# old_line_kick.net
KiCad netlist of a schematic drawn in EAGLE
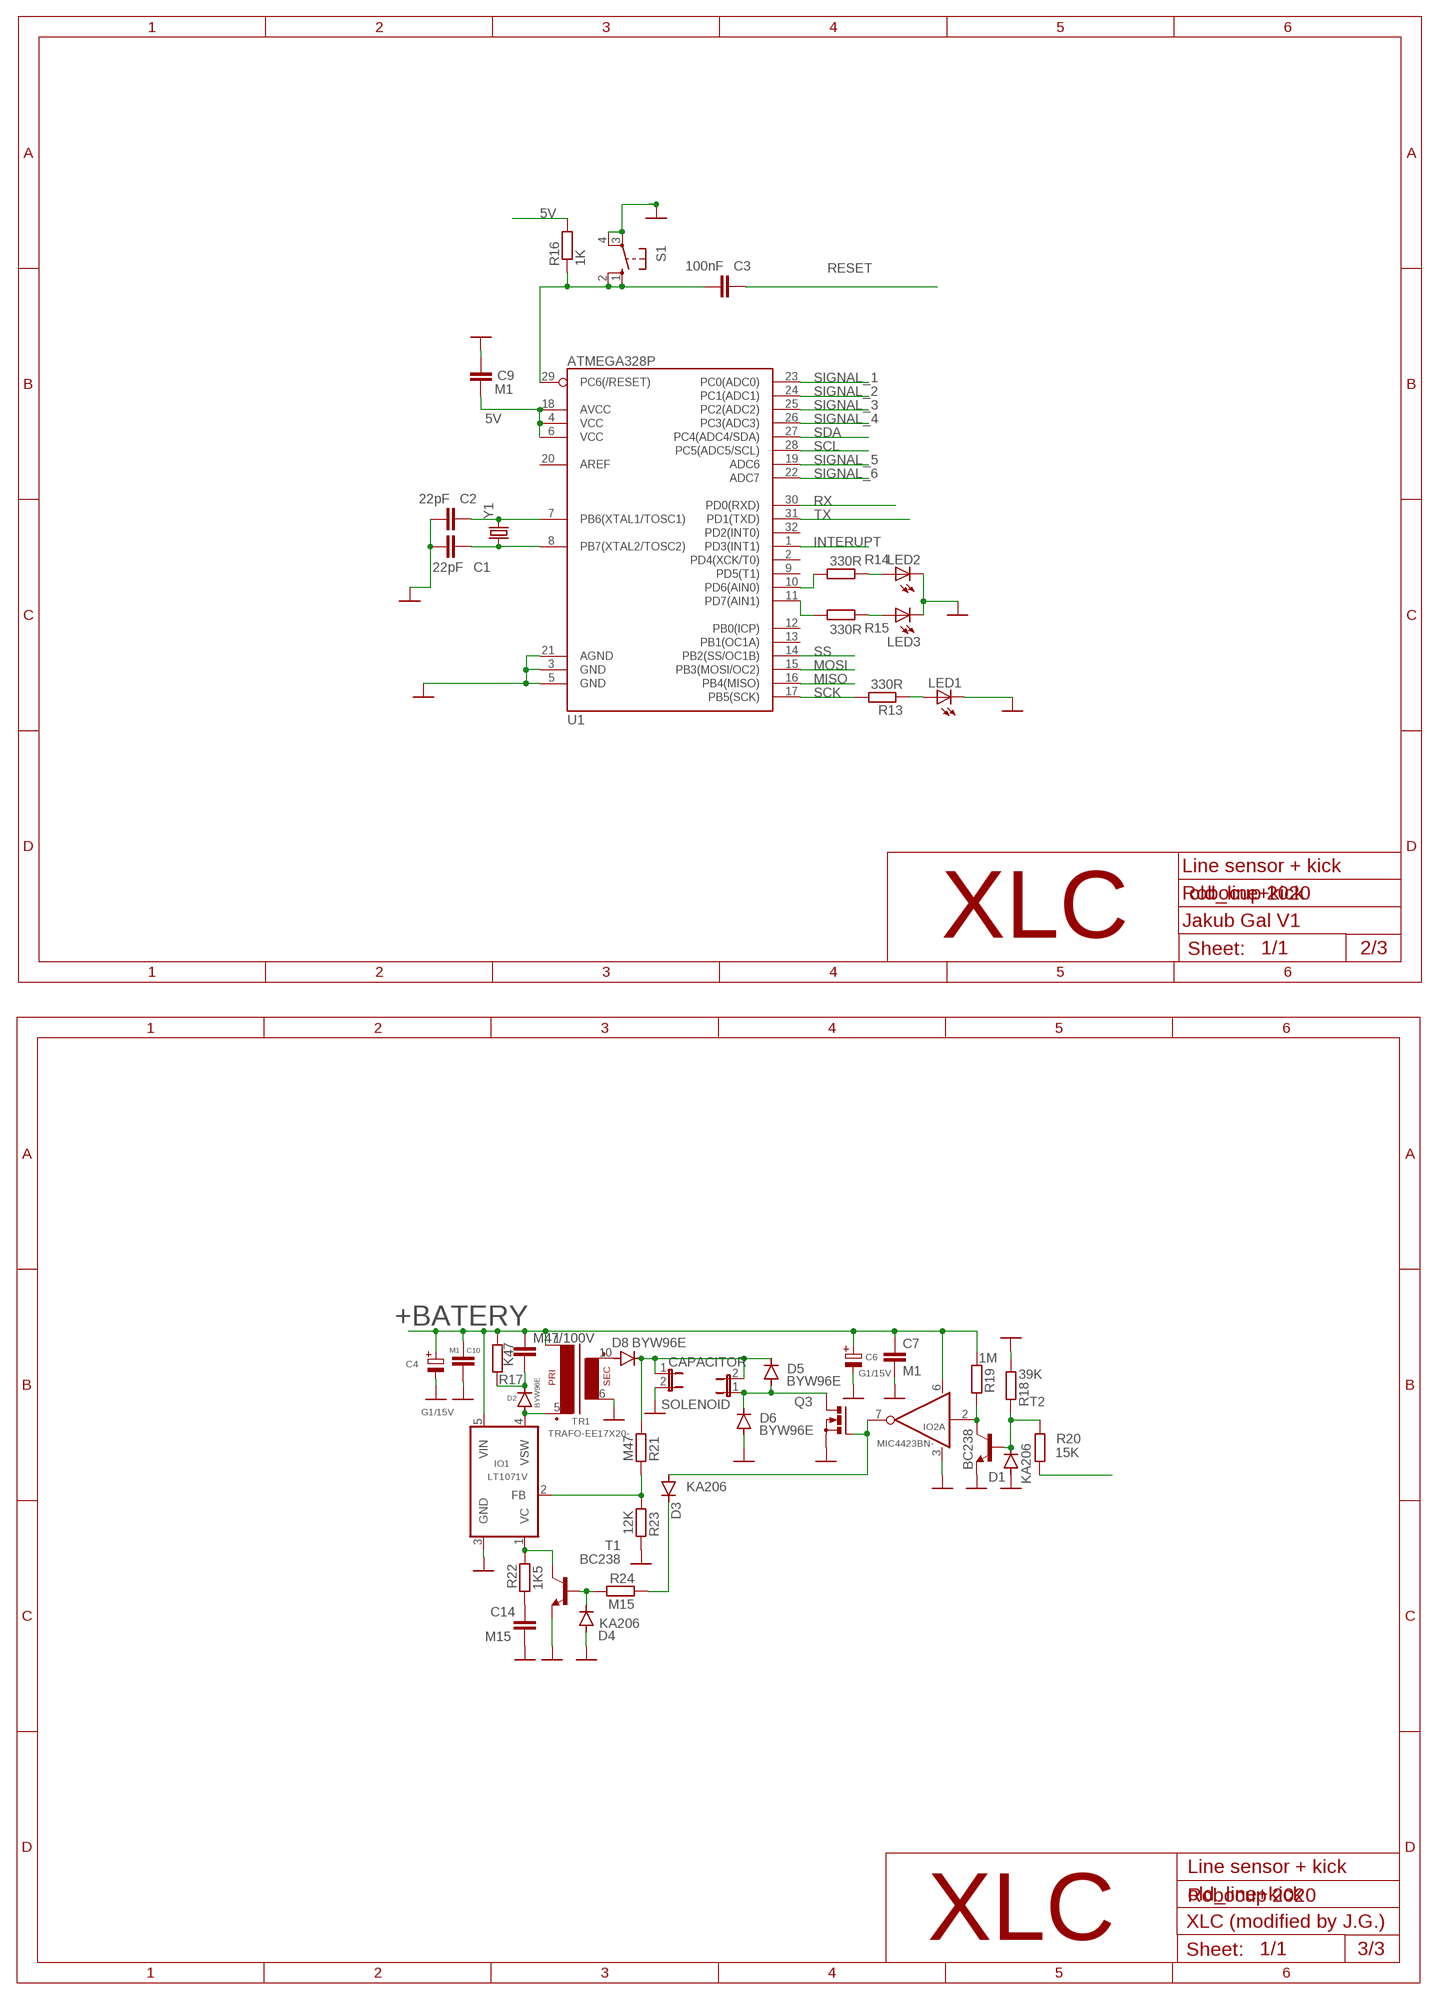
[diagram p0: schematic, sheet 1, part 1 of 2]
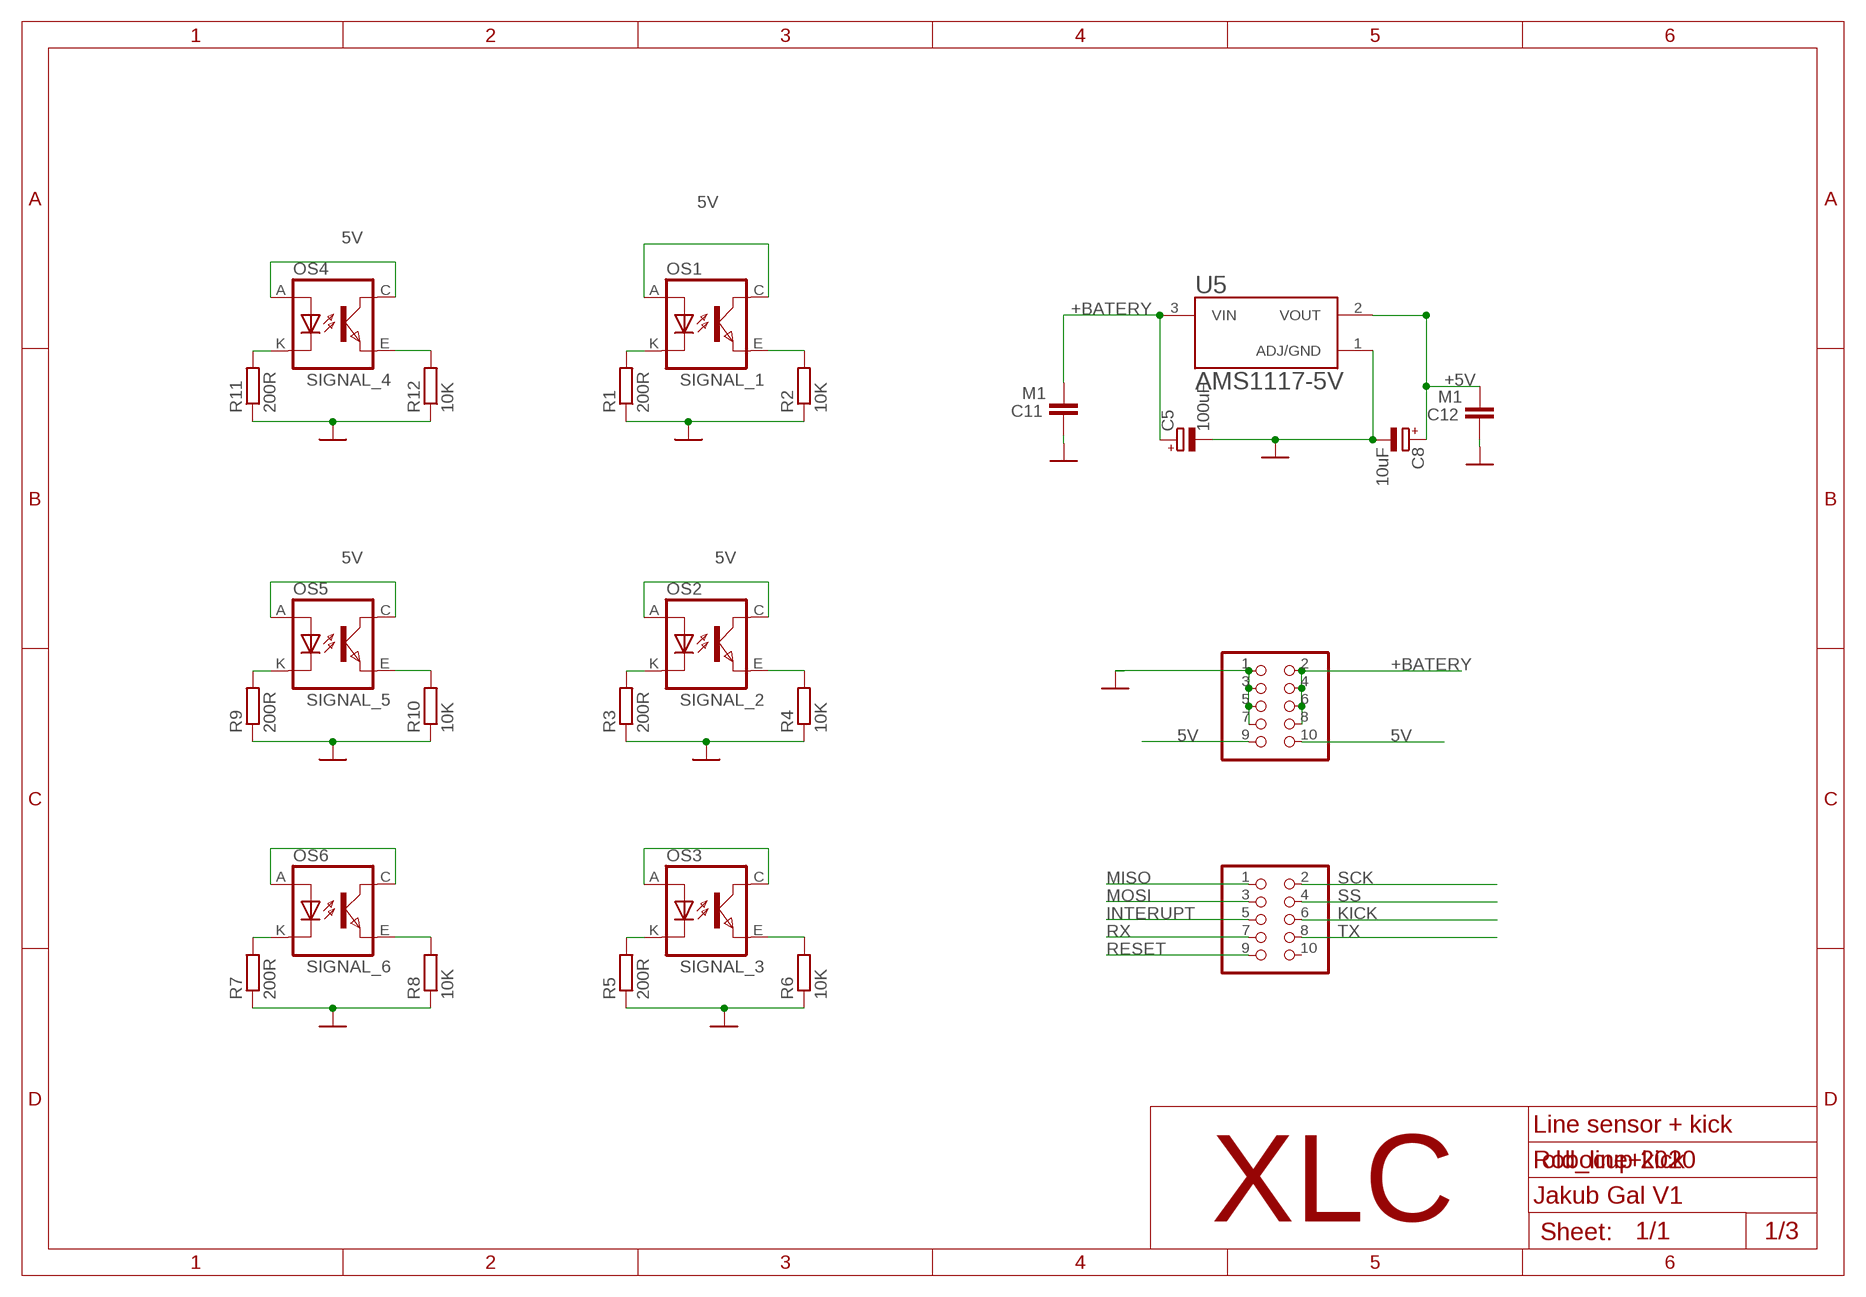
[diagram p1: schematic, sheet 1, part 2 of 2]

(export (version "E")
  (design (tool "Eeschema 10.0.6"))
  (components
    (comp (ref "C1")
      (value "22pF")
      (footprint "eagle-import:C0603")
      (libsource (lib "eagle-import") (part "C-EUC0603"))
    )
    (comp (ref "C2")
      (value "22pF")
      (footprint "eagle-import:C0603")
      (libsource (lib "eagle-import") (part "C-EUC0603"))
    )
    (comp (ref "C3")
      (value "100nF")
      (footprint "eagle-import:C0603")
      (libsource (lib "eagle-import") (part "C-EUC0603"))
    )
    (comp (ref "C4")
      (value "G1/15V")
      (footprint "eagle-import:E-2,5_7-RAD")
      (libsource (lib "eagle-import") (part "KOND-ELEKT-2,5/7"))
    )
    (comp (ref "C5")
      (value "100uF")
      (footprint "eagle-import:UD-6,3X7,7_NICHICON")
      (libsource (lib "eagle-import") (part "CPOL-EUUD-6,3X7,7"))
    )
    (comp (ref "C6")
      (value "G1/15V")
      (footprint "eagle-import:E-2,5_7-RAD")
      (libsource (lib "eagle-import") (part "KOND-ELEKT-2,5/7"))
    )
    (comp (ref "C7")
      (value "M1")
      (footprint "eagle-import:C0805K")
      (libsource (lib "eagle-import") (part "resistor_C-EUC0805K"))
    )
    (comp (ref "C8")
      (value "10uF")
      (footprint "eagle-import:UD-4X5,8_NICHICON")
      (libsource (lib "eagle-import") (part "CPOL-EUUD-4X5,8"))
    )
    (comp (ref "C9")
      (value "M1")
      (footprint "eagle-import:C0603")
      (libsource (lib "eagle-import") (part "C-EUC0603"))
    )
    (comp (ref "C10")
      (value "M1")
      (footprint "eagle-import:C0805K")
      (libsource (lib "eagle-import") (part "resistor_C-EUC0805K"))
    )
    (comp (ref "C11")
      (value "M1")
      (footprint "eagle-import:C0603")
      (libsource (lib "eagle-import") (part "C-EUC0603"))
    )
    (comp (ref "C12")
      (value "M1")
      (footprint "eagle-import:C0603")
      (libsource (lib "eagle-import") (part "C-EUC0603"))
    )
    (comp (ref "C14")
      (value "M15")
      (footprint "eagle-import:C0805K")
      (libsource (lib "eagle-import") (part "resistor_C-EUC0805K"))
    )
    (comp (ref "CAPACITOR")
      (value "JP1E")
      (footprint "eagle-import:JP1")
      (libsource (lib "eagle-import") (part "JP1E"))
    )
    (comp (ref "D1")
      (value "KA206")
      (footprint "eagle-import:D-7.5")
      (libsource (lib "eagle-import") (part "DIODE-D-7.5"))
    )
    (comp (ref "D2")
      (value "BYW96E")
      (footprint "eagle-import:SOD64-10")
      (libsource (lib "eagle-import") (part "BYW96"))
    )
    (comp (ref "D3")
      (value "KA206")
      (footprint "eagle-import:D-7.5")
      (libsource (lib "eagle-import") (part "DIODE-D-7.5"))
    )
    (comp (ref "D4")
      (value "KA206")
      (footprint "eagle-import:D-7.5")
      (libsource (lib "eagle-import") (part "DIODE-D-7.5"))
    )
    (comp (ref "D5")
      (value "BYW96E")
      (footprint "eagle-import:SOD64-10")
      (libsource (lib "eagle-import") (part "BYW96"))
    )
    (comp (ref "D6")
      (value "BYW96E")
      (footprint "eagle-import:SOD64-10")
      (libsource (lib "eagle-import") (part "BYW96"))
    )
    (comp (ref "D8")
      (value "BYW96E")
      (footprint "eagle-import:SOD64-10")
      (libsource (lib "eagle-import") (part "BYW96"))
    )
    (comp (ref "IO1")
      (value "LT1071V")
      (footprint "eagle-import:TO-220-5P")
      (libsource (lib "eagle-import") (part "LT1071V"))
    )
    (comp (ref "IO2")
      (value "MIC4423BN-")
      (footprint "eagle-import:DIL8")
      (libsource (lib "eagle-import") (part "MIC4423BN-"))
    )
    (comp (ref "JP2")
      (value "PINHD-2X5")
      (footprint "eagle-import:2X05")
      (libsource (lib "eagle-import") (part "PINHD-2X5"))
    )
    (comp (ref "JP3")
      (value "PINHD-2X5")
      (footprint "eagle-import:2X05")
      (libsource (lib "eagle-import") (part "PINHD-2X5"))
    )
    (comp (ref "LED1")
      (value "LEDCHIPLED_0603")
      (footprint "eagle-import:CHIPLED_0603")
      (libsource (lib "eagle-import") (part "LEDCHIPLED_0603"))
    )
    (comp (ref "LED2")
      (value "LEDCHIPLED_0603")
      (footprint "eagle-import:CHIPLED_0603")
      (libsource (lib "eagle-import") (part "LEDCHIPLED_0603"))
    )
    (comp (ref "LED3")
      (value "LEDCHIPLED_0603")
      (footprint "eagle-import:CHIPLED_0603")
      (libsource (lib "eagle-import") (part "LEDCHIPLED_0603"))
    )
    (comp (ref "M47/100V")
      (value "C-EUC0805K")
      (footprint "eagle-import:C0805K")
      (libsource (lib "eagle-import") (part "resistor_C-EUC0805K"))
    )
    (comp (ref "OS1")
      (value "TCRT5000")
      (footprint "eagle-import:TCRT5000")
      (libsource (lib "eagle-import") (part "TCRT5000"))
    )
    (comp (ref "OS2")
      (value "TCRT5000")
      (footprint "eagle-import:TCRT5000")
      (libsource (lib "eagle-import") (part "TCRT5000"))
    )
    (comp (ref "OS3")
      (value "TCRT5000")
      (footprint "eagle-import:TCRT5000")
      (libsource (lib "eagle-import") (part "TCRT5000"))
    )
    (comp (ref "OS4")
      (value "TCRT5000")
      (footprint "eagle-import:TCRT5000")
      (fields (field (name "SPICEPREFIX") "O"))
      (libsource (lib "eagle-import") (part "TCRT5000"))
    )
    (comp (ref "OS5")
      (value "TCRT5000")
      (footprint "eagle-import:TCRT5000")
      (libsource (lib "eagle-import") (part "TCRT5000"))
    )
    (comp (ref "OS6")
      (value "TCRT5000")
      (footprint "eagle-import:TCRT5000")
      (fields (field (name "SPICEPREFIX") "O"))
      (libsource (lib "eagle-import") (part "TCRT5000"))
    )
    (comp (ref "Q3")
      (value "PMOSFET_NTO220BV")
      (footprint "eagle-import:TO220BV")
      (libsource (lib "eagle-import") (part "PMOSFET_NTO220BV"))
    )
    (comp (ref "R1")
      (value "200R")
      (footprint "eagle-import:R0603")
      (libsource (lib "eagle-import") (part "R-EU_R0603"))
    )
    (comp (ref "R2")
      (value "10K")
      (footprint "eagle-import:R0603")
      (libsource (lib "eagle-import") (part "R-EU_R0603"))
    )
    (comp (ref "R3")
      (value "200R")
      (footprint "eagle-import:R0603")
      (libsource (lib "eagle-import") (part "R-EU_R0603"))
    )
    (comp (ref "R4")
      (value "10K")
      (footprint "eagle-import:R0603")
      (libsource (lib "eagle-import") (part "R-EU_R0603"))
    )
    (comp (ref "R5")
      (value "200R")
      (footprint "eagle-import:R0603")
      (libsource (lib "eagle-import") (part "R-EU_R0603"))
    )
    (comp (ref "R6")
      (value "10K")
      (footprint "eagle-import:R0603")
      (libsource (lib "eagle-import") (part "R-EU_R0603"))
    )
    (comp (ref "R7")
      (value "200R")
      (footprint "eagle-import:R0603")
      (libsource (lib "eagle-import") (part "R-EU_R0603"))
    )
    (comp (ref "R8")
      (value "10K")
      (footprint "eagle-import:R0603")
      (libsource (lib "eagle-import") (part "R-EU_R0603"))
    )
    (comp (ref "R9")
      (value "200R")
      (footprint "eagle-import:R0603")
      (libsource (lib "eagle-import") (part "R-EU_R0603"))
    )
    (comp (ref "R10")
      (value "10K")
      (footprint "eagle-import:R0603")
      (libsource (lib "eagle-import") (part "R-EU_R0603"))
    )
    (comp (ref "R11")
      (value "200R")
      (footprint "eagle-import:R0603")
      (libsource (lib "eagle-import") (part "R-EU_R0603"))
    )
    (comp (ref "R12")
      (value "10K")
      (footprint "eagle-import:R0603")
      (libsource (lib "eagle-import") (part "R-EU_R0603"))
    )
    (comp (ref "R13")
      (value "330R")
      (footprint "eagle-import:R0603")
      (libsource (lib "eagle-import") (part "R-EU_R0603"))
    )
    (comp (ref "R14")
      (value "330R")
      (footprint "eagle-import:R0603")
      (libsource (lib "eagle-import") (part "R-EU_R0603"))
    )
    (comp (ref "R15")
      (value "330R")
      (footprint "eagle-import:R0603")
      (libsource (lib "eagle-import") (part "R-EU_R0603"))
    )
    (comp (ref "R16")
      (value "1K")
      (footprint "eagle-import:R0603")
      (libsource (lib "eagle-import") (part "R-EU_R0603"))
    )
    (comp (ref "R17")
      (value "K47")
      (footprint "eagle-import:R0603")
      (libsource (lib "eagle-import") (part "resistor_R-EU_R0603"))
    )
    (comp (ref "R18")
      (value "39K")
      (footprint "eagle-import:R0603")
      (libsource (lib "eagle-import") (part "resistor_R-EU_R0603"))
    )
    (comp (ref "R19")
      (value "1M")
      (footprint "eagle-import:R0603")
      (libsource (lib "eagle-import") (part "resistor_R-EU_R0603"))
    )
    (comp (ref "R20")
      (value "15K")
      (footprint "eagle-import:R0603")
      (libsource (lib "eagle-import") (part "resistor_R-EU_R0603"))
    )
    (comp (ref "R21")
      (value "M47")
      (footprint "eagle-import:R0603")
      (libsource (lib "eagle-import") (part "resistor_R-EU_R0603"))
    )
    (comp (ref "R22")
      (value "1K5")
      (footprint "eagle-import:R0603")
      (libsource (lib "eagle-import") (part "resistor_R-EU_R0603"))
    )
    (comp (ref "R23")
      (value "12K")
      (footprint "eagle-import:R0603")
      (libsource (lib "eagle-import") (part "resistor_R-EU_R0603"))
    )
    (comp (ref "R24")
      (value "M15")
      (footprint "eagle-import:R0603")
      (libsource (lib "eagle-import") (part "resistor_R-EU_R0603"))
    )
    (comp (ref "S1")
      (value "10-XX")
      (footprint "eagle-import:B3F-10XX")
      (fields (field (name "MPN") "B3F-1000"))
      (libsource (lib "eagle-import") (part "10-XX"))
    )
    (comp (ref "SOLENOID")
      (value "JP1E")
      (footprint "eagle-import:JP1")
      (libsource (lib "eagle-import") (part "JP1E"))
    )
    (comp (ref "T1")
      (value "BC238")
      (footprint "eagle-import:TO92")
      (libsource (lib "eagle-import") (part "BC238"))
    )
    (comp (ref "T2")
      (value "BC238")
      (footprint "eagle-import:TO92")
      (libsource (lib "eagle-import") (part "BC238"))
    )
    (comp (ref "TR1")
      (value "TRAFO-EE17X20-")
      (footprint "eagle-import:TRAFO-EE17X20")
      (libsource (lib "eagle-import") (part "TRAFO-EE17X20-"))
    )
    (comp (ref "U1")
      (value "ATMEGA328P")
      (footprint "eagle-import:TQFP32-08")
      (libsource (lib "eagle-import") (part "ATMEGA328_SMT"))
    )
    (comp (ref "U5")
      (value "AMS1117-5V")
      (footprint "eagle-import:SOT229P700X180-4N")
      (fields (field (name "MF") "Advanced Monolithic Systems") (field (name "MP") "AMS1117-3.3"))
      (libsource (lib "eagle-import") (part "AMS1117-3.3"))
    )
    (comp (ref "Y1")
      (value "CRYSTALHC49US")
      (footprint "eagle-import:HC49US")
      (libsource (lib "eagle-import") (part "CRYSTALHC49US"))
    )
  )
  (nets
    (net (code "1") (name "/+5V") (class "Default")
      (node (ref "C12") (pin "1") (pinfunction "1_1") (pintype "passive"))
      (node (ref "C8") (pin "+") (pinfunction "+_+") (pintype "passive"))
      (node (ref "U5") (pin "2") (pinfunction "VOUT_2") (pintype "output"))
    )
    (net (code "2") (name "/+BATERY") (class "Default")
      (node (ref "C10") (pin "1") (pinfunction "1_1") (pintype "passive"))
      (node (ref "C11") (pin "1") (pinfunction "1_1") (pintype "passive"))
      (node (ref "C4") (pin "+") (pinfunction "+_+") (pintype "passive"))
      (node (ref "C5") (pin "+") (pinfunction "+_+") (pintype "passive"))
      (node (ref "C6") (pin "+") (pinfunction "+_+") (pintype "passive"))
      (node (ref "C7") (pin "1") (pinfunction "1_1") (pintype "passive"))
      (node (ref "IO1") (pin "5") (pinfunction "VIN_5") (pintype "power_in"))
      (node (ref "IO2") (pin "6") (pinfunction "VCC_6") (pintype "power_in"))
      (node (ref "JP3") (pin "2") (pinfunction "2_2") (pintype "passive"))
      (node (ref "JP3") (pin "4") (pinfunction "4_4") (pintype "passive"))
      (node (ref "JP3") (pin "6") (pinfunction "6_6") (pintype "passive"))
      (node (ref "JP3") (pin "8") (pinfunction "8_8") (pintype "passive"))
      (node (ref "M47/100V") (pin "1") (pinfunction "1_1") (pintype "passive"))
      (node (ref "R17") (pin "1") (pinfunction "1_1") (pintype "passive"))
      (node (ref "R19") (pin "2") (pinfunction "2_2") (pintype "passive"))
      (node (ref "TR1") (pin "1") (pinfunction "1_1") (pintype "passive"))
      (node (ref "U5") (pin "3") (pinfunction "VIN_3") (pintype "input"))
    )
    (net (code "3") (name "/5V") (class "Default")
      (node (ref "C9") (pin "1") (pinfunction "1_1") (pintype "passive"))
      (node (ref "JP3") (pin "10") (pinfunction "10_10") (pintype "passive"))
      (node (ref "JP3") (pin "9") (pinfunction "9_9") (pintype "passive"))
      (node (ref "OS1") (pin "A") (pinfunction "ANODE_A") (pintype "passive"))
      (node (ref "OS1") (pin "C") (pinfunction "COLLECTOR_C") (pintype "passive"))
      (node (ref "OS2") (pin "A") (pinfunction "ANODE_A") (pintype "passive"))
      (node (ref "OS2") (pin "C") (pinfunction "COLLECTOR_C") (pintype "passive"))
      (node (ref "OS3") (pin "A") (pinfunction "ANODE_A") (pintype "passive"))
      (node (ref "OS3") (pin "C") (pinfunction "COLLECTOR_C") (pintype "passive"))
      (node (ref "OS4") (pin "A") (pinfunction "ANODE_A") (pintype "passive"))
      (node (ref "OS4") (pin "C") (pinfunction "COLLECTOR_C") (pintype "passive"))
      (node (ref "OS5") (pin "A") (pinfunction "ANODE_A") (pintype "passive"))
      (node (ref "OS5") (pin "C") (pinfunction "COLLECTOR_C") (pintype "passive"))
      (node (ref "OS6") (pin "A") (pinfunction "ANODE_A") (pintype "passive"))
      (node (ref "OS6") (pin "C") (pinfunction "COLLECTOR_C") (pintype "passive"))
      (node (ref "R16") (pin "2") (pinfunction "2_2") (pintype "passive"))
      (node (ref "U1") (pin "18") (pinfunction "AVCC_18") (pintype "bidirectional"))
      (node (ref "U1") (pin "4") (pinfunction "VCC_4") (pintype "bidirectional"))
      (node (ref "U1") (pin "6") (pinfunction "VCC_6") (pintype "bidirectional"))
    )
    (net (code "4") (name "/INTERUPT") (class "Default")
      (node (ref "JP2") (pin "5") (pinfunction "5_5") (pintype "passive"))
      (node (ref "U1") (pin "1") (pinfunction "PD3(INT1)_1") (pintype "bidirectional"))
    )
    (net (code "5") (name "/KICK") (class "Default")
      (node (ref "JP2") (pin "6") (pinfunction "6_6") (pintype "passive"))
      (node (ref "R20") (pin "1") (pinfunction "1_1") (pintype "passive"))
    )
    (net (code "6") (name "/MISO") (class "Default")
      (node (ref "JP2") (pin "1") (pinfunction "1_1") (pintype "passive"))
      (node (ref "U1") (pin "16") (pinfunction "PB4(MISO)_16") (pintype "bidirectional"))
    )
    (net (code "7") (name "/MOSI") (class "Default")
      (node (ref "JP2") (pin "3") (pinfunction "3_3") (pintype "passive"))
      (node (ref "U1") (pin "15") (pinfunction "PB3(MOSI/OC2)_15") (pintype "bidirectional"))
    )
    (net (code "8") (name "/RESET") (class "Default")
      (node (ref "C3") (pin "2") (pinfunction "2_2") (pintype "passive"))
      (node (ref "JP2") (pin "9") (pinfunction "9_9") (pintype "passive"))
    )
    (net (code "9") (name "/RX") (class "Default")
      (node (ref "JP2") (pin "7") (pinfunction "7_7") (pintype "passive"))
      (node (ref "U1") (pin "30") (pinfunction "PD0(RXD)_30") (pintype "bidirectional"))
    )
    (net (code "10") (name "/SCK") (class "Default")
      (node (ref "JP2") (pin "2") (pinfunction "2_2") (pintype "passive"))
      (node (ref "R13") (pin "2") (pinfunction "2_2") (pintype "passive"))
      (node (ref "U1") (pin "17") (pinfunction "PB5(SCK)_17") (pintype "bidirectional"))
    )
    (net (code "11") (name "/SCL") (class "Default")
      (node (ref "U1") (pin "28") (pinfunction "PC5(ADC5/SCL)_28") (pintype "bidirectional"))
    )
    (net (code "12") (name "/SDA") (class "Default")
      (node (ref "U1") (pin "27") (pinfunction "PC4(ADC4/SDA)_27") (pintype "bidirectional"))
    )
    (net (code "13") (name "/SIGNAL_1") (class "Default")
      (node (ref "OS1") (pin "E") (pinfunction "EMITTER_E") (pintype "passive"))
      (node (ref "R2") (pin "2") (pinfunction "2_2") (pintype "passive"))
      (node (ref "U1") (pin "23") (pinfunction "PC0(ADC0)_23") (pintype "bidirectional"))
    )
    (net (code "14") (name "/SIGNAL_2") (class "Default")
      (node (ref "OS2") (pin "E") (pinfunction "EMITTER_E") (pintype "passive"))
      (node (ref "R4") (pin "2") (pinfunction "2_2") (pintype "passive"))
      (node (ref "U1") (pin "24") (pinfunction "PC1(ADC1)_24") (pintype "bidirectional"))
    )
    (net (code "15") (name "/SIGNAL_3") (class "Default")
      (node (ref "OS3") (pin "E") (pinfunction "EMITTER_E") (pintype "passive"))
      (node (ref "R6") (pin "2") (pinfunction "2_2") (pintype "passive"))
      (node (ref "U1") (pin "25") (pinfunction "PC2(ADC2)_25") (pintype "bidirectional"))
    )
    (net (code "16") (name "/SIGNAL_4") (class "Default")
      (node (ref "OS4") (pin "E") (pinfunction "EMITTER_E") (pintype "passive"))
      (node (ref "R12") (pin "2") (pinfunction "2_2") (pintype "passive"))
      (node (ref "U1") (pin "26") (pinfunction "PC3(ADC3)_26") (pintype "bidirectional"))
    )
    (net (code "17") (name "/SIGNAL_5") (class "Default")
      (node (ref "OS5") (pin "E") (pinfunction "EMITTER_E") (pintype "passive"))
      (node (ref "R10") (pin "2") (pinfunction "2_2") (pintype "passive"))
      (node (ref "U1") (pin "19") (pinfunction "ADC6_19") (pintype "bidirectional"))
    )
    (net (code "18") (name "/SIGNAL_6") (class "Default")
      (node (ref "OS6") (pin "E") (pinfunction "EMITTER_E") (pintype "passive"))
      (node (ref "R8") (pin "2") (pinfunction "2_2") (pintype "passive"))
      (node (ref "U1") (pin "22") (pinfunction "ADC7_22") (pintype "bidirectional"))
    )
    (net (code "19") (name "/SS") (class "Default")
      (node (ref "JP2") (pin "4") (pinfunction "4_4") (pintype "passive"))
      (node (ref "U1") (pin "14") (pinfunction "PB2(SS/OC1B)_14") (pintype "bidirectional"))
    )
    (net (code "20") (name "/TX") (class "Default")
      (node (ref "JP2") (pin "8") (pinfunction "8_8") (pintype "passive"))
      (node (ref "U1") (pin "31") (pinfunction "PD1(TXD)_31") (pintype "bidirectional"))
    )
    (net (code "21") (name "GND") (class "Default")
      (node (ref "C1") (pin "1") (pinfunction "1_1") (pintype "passive"))
      (node (ref "C10") (pin "2") (pinfunction "2_2") (pintype "passive"))
      (node (ref "C11") (pin "2") (pinfunction "2_2") (pintype "passive"))
      (node (ref "C12") (pin "2") (pinfunction "2_2") (pintype "passive"))
      (node (ref "C14") (pin "2") (pinfunction "2_2") (pintype "passive"))
      (node (ref "C2") (pin "1") (pinfunction "1_1") (pintype "passive"))
      (node (ref "C4") (pin "-") (pinfunction "-_-") (pintype "passive"))
      (node (ref "C5") (pin "-") (pinfunction "-_-") (pintype "passive"))
      (node (ref "C6") (pin "-") (pinfunction "-_-") (pintype "passive"))
      (node (ref "C7") (pin "2") (pinfunction "2_2") (pintype "passive"))
      (node (ref "C8") (pin "-") (pinfunction "-_-") (pintype "passive"))
      (node (ref "C9") (pin "2") (pinfunction "2_2") (pintype "passive"))
      (node (ref "CAPACITOR") (pin "2") (pinfunction "2_2") (pintype "passive"))
      (node (ref "D1") (pin "A") (pinfunction "A_A") (pintype "passive"))
      (node (ref "D4") (pin "A") (pinfunction "A_A") (pintype "passive"))
      (node (ref "D6") (pin "A") (pinfunction "A_A") (pintype "passive"))
      (node (ref "IO1") (pin "3") (pinfunction "GND_3") (pintype "power_in"))
      (node (ref "IO2") (pin "3") (pinfunction "GND_3") (pintype "power_in"))
      (node (ref "JP3") (pin "1") (pinfunction "1_1") (pintype "passive"))
      (node (ref "JP3") (pin "3") (pinfunction "3_3") (pintype "passive"))
      (node (ref "JP3") (pin "5") (pinfunction "5_5") (pintype "passive"))
      (node (ref "JP3") (pin "7") (pinfunction "7_7") (pintype "passive"))
      (node (ref "LED1") (pin "C") (pinfunction "C_C") (pintype "passive"))
      (node (ref "LED2") (pin "C") (pinfunction "C_C") (pintype "passive"))
      (node (ref "LED3") (pin "C") (pinfunction "C_C") (pintype "passive"))
      (node (ref "Q3") (pin "S") (pinfunction "S_S") (pintype "passive"))
      (node (ref "R1") (pin "1") (pinfunction "1_1") (pintype "passive"))
      (node (ref "R10") (pin "1") (pinfunction "1_1") (pintype "passive"))
      (node (ref "R11") (pin "1") (pinfunction "1_1") (pintype "passive"))
      (node (ref "R12") (pin "1") (pinfunction "1_1") (pintype "passive"))
      (node (ref "R18") (pin "2") (pinfunction "2_2") (pintype "passive"))
      (node (ref "R2") (pin "1") (pinfunction "1_1") (pintype "passive"))
      (node (ref "R23") (pin "1") (pinfunction "1_1") (pintype "passive"))
      (node (ref "R3") (pin "1") (pinfunction "1_1") (pintype "passive"))
      (node (ref "R4") (pin "1") (pinfunction "1_1") (pintype "passive"))
      (node (ref "R5") (pin "1") (pinfunction "1_1") (pintype "passive"))
      (node (ref "R6") (pin "1") (pinfunction "1_1") (pintype "passive"))
      (node (ref "R7") (pin "1") (pinfunction "1_1") (pintype "passive"))
      (node (ref "R8") (pin "1") (pinfunction "1_1") (pintype "passive"))
      (node (ref "R9") (pin "1") (pinfunction "1_1") (pintype "passive"))
      (node (ref "S1") (pin "3") (pinfunction "P_3") (pintype "passive"))
      (node (ref "S1") (pin "4") (pinfunction "P1_4") (pintype "passive"))
      (node (ref "T1") (pin "1") (pinfunction "E_1") (pintype "passive"))
      (node (ref "T2") (pin "1") (pinfunction "E_1") (pintype "passive"))
      (node (ref "TR1") (pin "6") (pinfunction "3_6") (pintype "passive"))
      (node (ref "U1") (pin "21") (pinfunction "AGND_21") (pintype "bidirectional"))
      (node (ref "U1") (pin "3") (pinfunction "GND_3") (pintype "bidirectional"))
      (node (ref "U1") (pin "5") (pinfunction "GND_5") (pintype "bidirectional"))
      (node (ref "U5") (pin "1") (pinfunction "ADJ/GND_1") (pintype "power_in"))
    )
    (net (code "22") (name "Net-(C14-Pad1)") (class "Default")
      (node (ref "C14") (pin "1") (pinfunction "1_1") (pintype "passive"))
      (node (ref "R22") (pin "2") (pinfunction "2_2") (pintype "passive"))
    )
    (net (code "23") (name "Net-(CAPACITOR-Pad1)") (class "Default")
      (node (ref "CAPACITOR") (pin "1") (pinfunction "1_1") (pintype "passive"))
      (node (ref "D5") (pin "C") (pinfunction "C_C") (pintype "passive"))
      (node (ref "D8") (pin "C") (pinfunction "C_C") (pintype "passive"))
      (node (ref "R21") (pin "2") (pinfunction "2_2") (pintype "passive"))
      (node (ref "SOLENOID") (pin "2") (pinfunction "2_2") (pintype "passive"))
    )
    (net (code "24") (name "Net-(D2-PadC)") (class "Default")
      (node (ref "D2") (pin "C") (pinfunction "C_C") (pintype "passive"))
      (node (ref "M47/100V") (pin "2") (pinfunction "2_2") (pintype "passive"))
      (node (ref "R17") (pin "2") (pinfunction "2_2") (pintype "passive"))
    )
    (net (code "25") (name "Net-(D3-PadC)") (class "Default")
      (node (ref "D3") (pin "C") (pinfunction "C_C") (pintype "passive"))
      (node (ref "R24") (pin "1") (pinfunction "1_1") (pintype "passive"))
    )
    (net (code "26") (name "Net-(D5-PadA)") (class "Default")
      (node (ref "D5") (pin "A") (pinfunction "A_A") (pintype "passive"))
      (node (ref "D6") (pin "C") (pinfunction "C_C") (pintype "passive"))
      (node (ref "Q3") (pin "D") (pinfunction "D_D") (pintype "passive"))
      (node (ref "SOLENOID") (pin "1") (pinfunction "1_1") (pintype "passive"))
    )
    (net (code "27") (name "Net-(IO1-FB)") (class "Default")
      (node (ref "IO1") (pin "2") (pinfunction "FB_2") (pintype "input"))
      (node (ref "R21") (pin "1") (pinfunction "1_1") (pintype "passive"))
      (node (ref "R23") (pin "2") (pinfunction "2_2") (pintype "passive"))
    )
    (net (code "28") (name "Net-(IO1-VC)") (class "Default")
      (node (ref "IO1") (pin "1") (pinfunction "VC_1") (pintype "input"))
      (node (ref "R22") (pin "1") (pinfunction "1_1") (pintype "passive"))
      (node (ref "T1") (pin "3") (pinfunction "C_3") (pintype "passive"))
    )
    (net (code "29") (name "Net-(IO1-VSW)") (class "Default")
      (node (ref "D2") (pin "A") (pinfunction "A_A") (pintype "passive"))
      (node (ref "IO1") (pin "4") (pinfunction "VSW_4") (pintype "output"))
      (node (ref "TR1") (pin "5") (pinfunction "2_5") (pintype "passive"))
    )
    (net (code "30") (name "Net-(IO2A-I)") (class "Default")
      (node (ref "IO2") (pin "2") (pinfunction "I_2") (pintype "input"))
      (node (ref "R19") (pin "1") (pinfunction "1_1") (pintype "passive"))
      (node (ref "T2") (pin "3") (pinfunction "C_3") (pintype "passive"))
    )
    (net (code "31") (name "Net-(IO2A-O)") (class "Default")
      (node (ref "D3") (pin "A") (pinfunction "A_A") (pintype "passive"))
      (node (ref "IO2") (pin "7") (pinfunction "O_7") (pintype "output"))
      (node (ref "Q3") (pin "G") (pinfunction "G_G") (pintype "passive"))
    )
    (net (code "32") (name "Net-(LED1-PadA)") (class "Default")
      (node (ref "LED1") (pin "A") (pinfunction "A_A") (pintype "passive"))
      (node (ref "R13") (pin "1") (pinfunction "1_1") (pintype "passive"))
    )
    (net (code "33") (name "Net-(LED2-PadA)") (class "Default")
      (node (ref "LED2") (pin "A") (pinfunction "A_A") (pintype "passive"))
      (node (ref "R14") (pin "1") (pinfunction "1_1") (pintype "passive"))
    )
    (net (code "34") (name "Net-(LED3-PadA)") (class "Default")
      (node (ref "LED3") (pin "A") (pinfunction "A_A") (pintype "passive"))
      (node (ref "R15") (pin "1") (pinfunction "1_1") (pintype "passive"))
    )
    (net (code "35") (name "Net-(OS1-CATHODE)") (class "Default")
      (node (ref "OS1") (pin "K") (pinfunction "CATHODE_K") (pintype "passive"))
      (node (ref "R1") (pin "2") (pinfunction "2_2") (pintype "passive"))
    )
    (net (code "36") (name "Net-(OS2-CATHODE)") (class "Default")
      (node (ref "OS2") (pin "K") (pinfunction "CATHODE_K") (pintype "passive"))
      (node (ref "R3") (pin "2") (pinfunction "2_2") (pintype "passive"))
    )
    (net (code "37") (name "Net-(OS3-CATHODE)") (class "Default")
      (node (ref "OS3") (pin "K") (pinfunction "CATHODE_K") (pintype "passive"))
      (node (ref "R5") (pin "2") (pinfunction "2_2") (pintype "passive"))
    )
    (net (code "38") (name "Net-(OS4-CATHODE)") (class "Default")
      (node (ref "OS4") (pin "K") (pinfunction "CATHODE_K") (pintype "passive"))
      (node (ref "R11") (pin "2") (pinfunction "2_2") (pintype "passive"))
    )
    (net (code "39") (name "Net-(OS5-CATHODE)") (class "Default")
      (node (ref "OS5") (pin "K") (pinfunction "CATHODE_K") (pintype "passive"))
      (node (ref "R9") (pin "2") (pinfunction "2_2") (pintype "passive"))
    )
    (net (code "40") (name "Net-(OS6-CATHODE)") (class "Default")
      (node (ref "OS6") (pin "K") (pinfunction "CATHODE_K") (pintype "passive"))
      (node (ref "R7") (pin "2") (pinfunction "2_2") (pintype "passive"))
    )
    (net (code "41") (name "Net-(S1-S)") (class "Default")
      (node (ref "C3") (pin "1") (pinfunction "1_1") (pintype "passive"))
      (node (ref "R16") (pin "1") (pinfunction "1_1") (pintype "passive"))
      (node (ref "S1") (pin "1") (pinfunction "S_1") (pintype "passive"))
      (node (ref "S1") (pin "2") (pinfunction "S1_2") (pintype "passive"))
      (node (ref "U1") (pin "29") (pinfunction "PC6(/RESET)_29") (pintype "bidirectional"))
    )
    (net (code "42") (name "Net-(T1-B)") (class "Default")
      (node (ref "D4") (pin "C") (pinfunction "C_C") (pintype "passive"))
      (node (ref "R24") (pin "2") (pinfunction "2_2") (pintype "passive"))
      (node (ref "T1") (pin "2") (pinfunction "B_2") (pintype "passive"))
    )
    (net (code "43") (name "Net-(T2-B)") (class "Default")
      (node (ref "D1") (pin "C") (pinfunction "C_C") (pintype "passive"))
      (node (ref "R18") (pin "1") (pinfunction "1_1") (pintype "passive"))
      (node (ref "R20") (pin "2") (pinfunction "2_2") (pintype "passive"))
      (node (ref "T2") (pin "2") (pinfunction "B_2") (pintype "passive"))
    )
    (net (code "44") (name "Net-(TR1-4)") (class "Default")
      (node (ref "D8") (pin "A") (pinfunction "A_A") (pintype "passive"))
      (node (ref "TR1") (pin "10") (pinfunction "4_10") (pintype "passive"))
    )
    (net (code "45") (name "Net-(U1-PB6(XTAL1{slash}TOSC1))") (class "Default")
      (node (ref "C2") (pin "2") (pinfunction "2_2") (pintype "passive"))
      (node (ref "U1") (pin "7") (pinfunction "PB6(XTAL1/TOSC1)_7") (pintype "bidirectional"))
      (node (ref "Y1") (pin "2") (pinfunction "2_2") (pintype "passive"))
    )
    (net (code "46") (name "Net-(U1-PB7(XTAL2{slash}TOSC2))") (class "Default")
      (node (ref "C1") (pin "2") (pinfunction "2_2") (pintype "passive"))
      (node (ref "U1") (pin "8") (pinfunction "PB7(XTAL2/TOSC2)_8") (pintype "bidirectional"))
      (node (ref "Y1") (pin "1") (pinfunction "1_1") (pintype "passive"))
    )
    (net (code "47") (name "Net-(U1-PD6(AIN0))") (class "Default")
      (node (ref "R14") (pin "2") (pinfunction "2_2") (pintype "passive"))
      (node (ref "U1") (pin "10") (pinfunction "PD6(AIN0)_10") (pintype "bidirectional"))
    )
    (net (code "48") (name "Net-(U1-PD7(AIN1))") (class "Default")
      (node (ref "R15") (pin "2") (pinfunction "2_2") (pintype "passive"))
      (node (ref "U1") (pin "11") (pinfunction "PD7(AIN1)_11") (pintype "bidirectional"))
    )
    (net (code "49") (name "unconnected-(JP2-Pad10)") (class "Default")
      (node (ref "JP2") (pin "10") (pinfunction "10_10") (pintype "passive"))
    )
    (net (code "50") (name "unconnected-(U1-AREF-Pad20)") (class "Default")
      (node (ref "U1") (pin "20") (pinfunction "AREF_20") (pintype "bidirectional"))
    )
    (net (code "51") (name "unconnected-(U1-PB0(ICP)-Pad12)") (class "Default")
      (node (ref "U1") (pin "12") (pinfunction "PB0(ICP)_12") (pintype "bidirectional"))
    )
    (net (code "52") (name "unconnected-(U1-PB1(OC1A)-Pad13)") (class "Default")
      (node (ref "U1") (pin "13") (pinfunction "PB1(OC1A)_13") (pintype "bidirectional"))
    )
    (net (code "53") (name "unconnected-(U1-PD2(INT0)-Pad32)") (class "Default")
      (node (ref "U1") (pin "32") (pinfunction "PD2(INT0)_32") (pintype "bidirectional"))
    )
    (net (code "54") (name "unconnected-(U1-PD4(XCK{slash}T0)-Pad2)") (class "Default")
      (node (ref "U1") (pin "2") (pinfunction "PD4(XCK/T0)_2") (pintype "bidirectional"))
    )
    (net (code "55") (name "unconnected-(U1-PD5(T1)-Pad9)") (class "Default")
      (node (ref "U1") (pin "9") (pinfunction "PD5(T1)_9") (pintype "bidirectional"))
    )
  )
)
